# Main_Board_v1.net
KiCad netlist of a schematic drawn in EAGLE
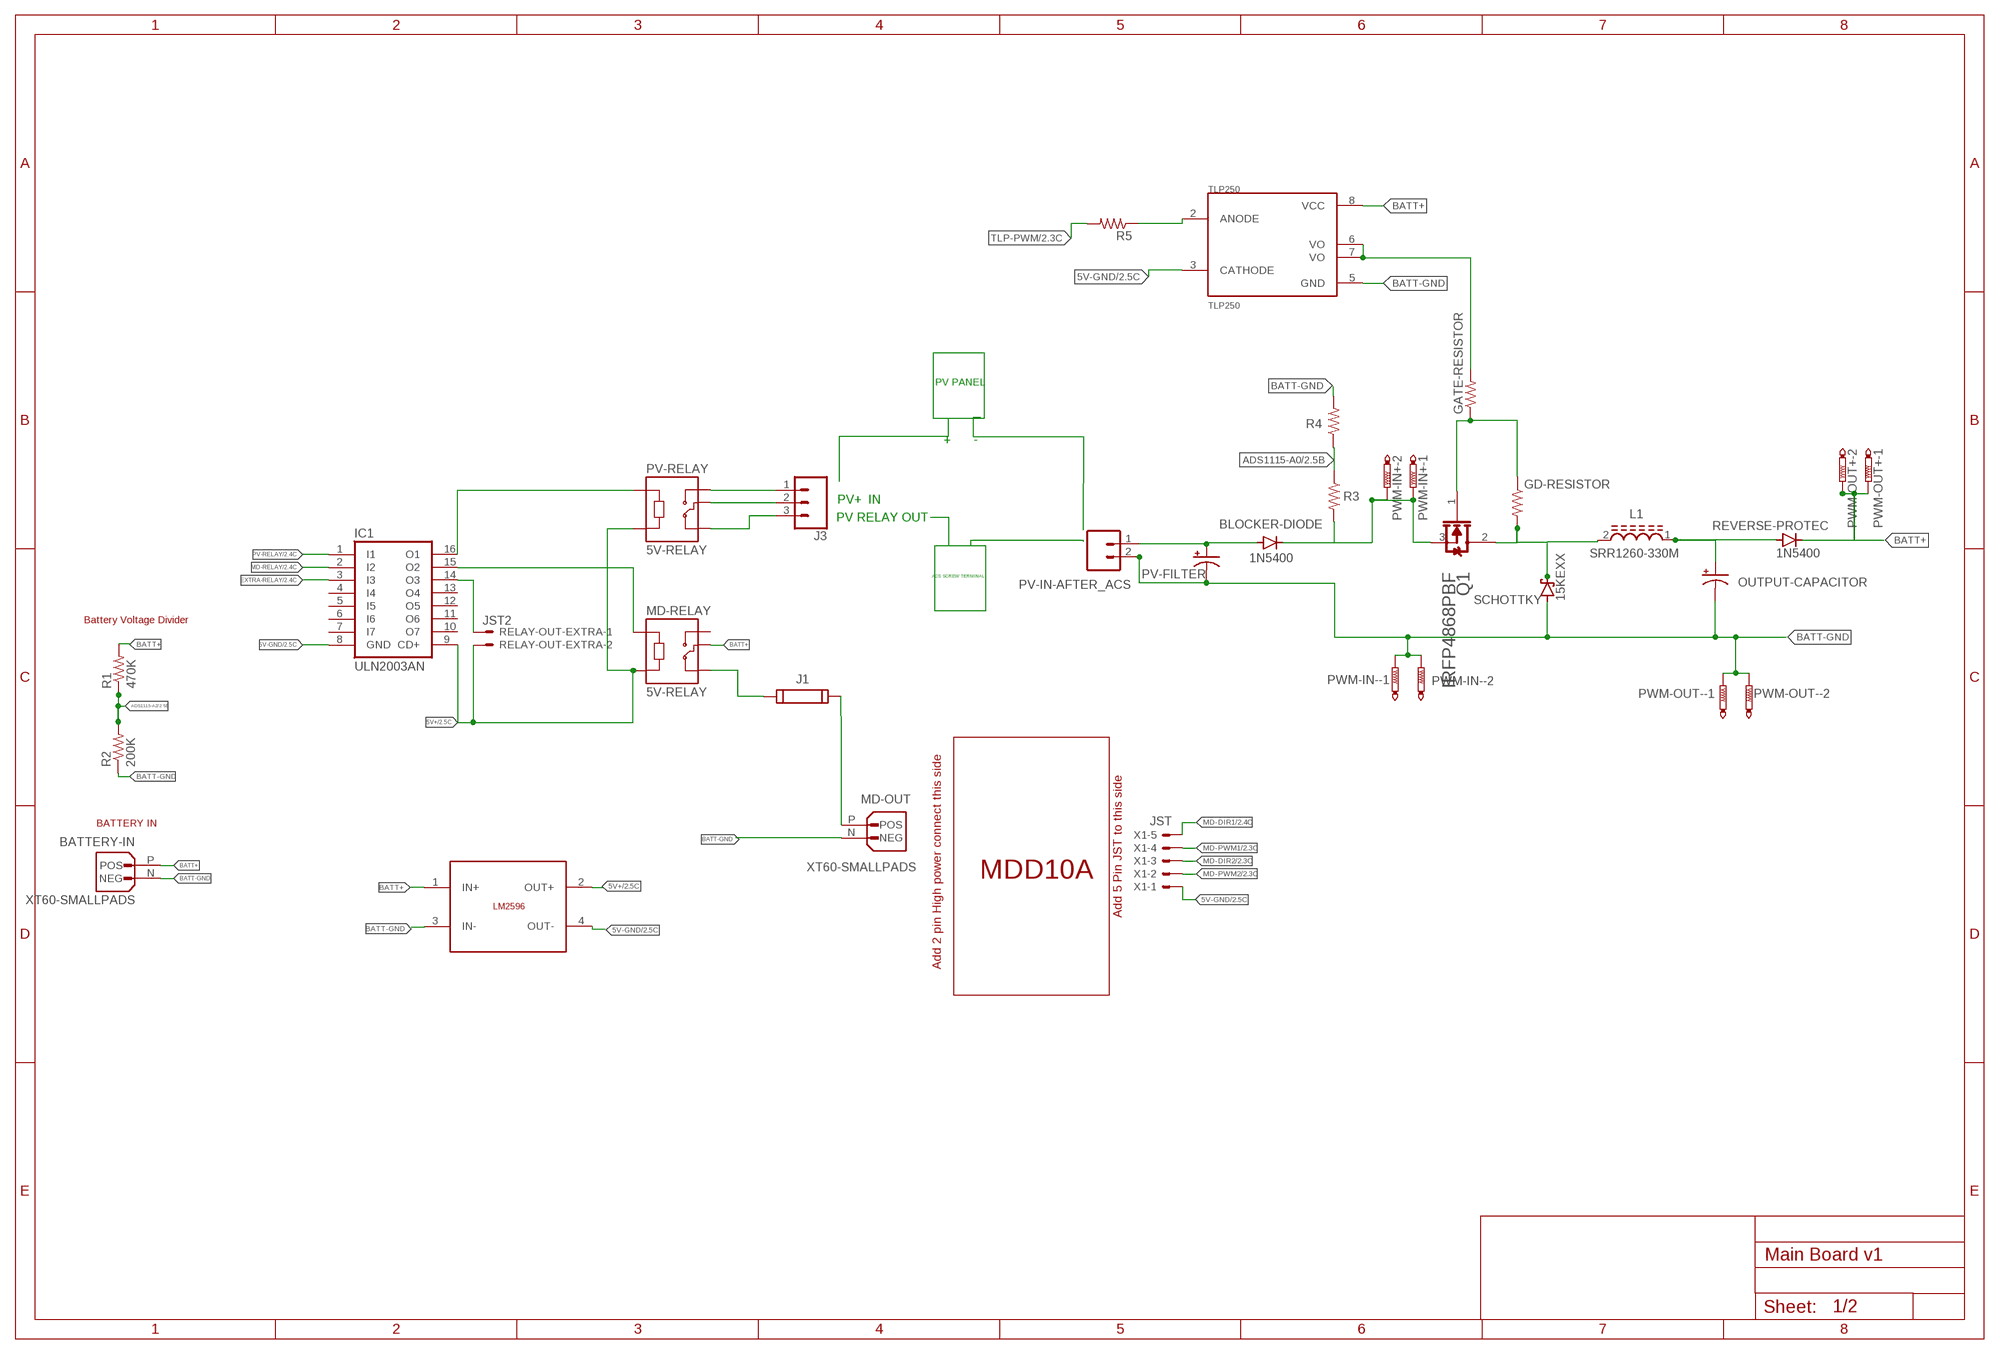
[diagram p0: schematic, sheet 1]
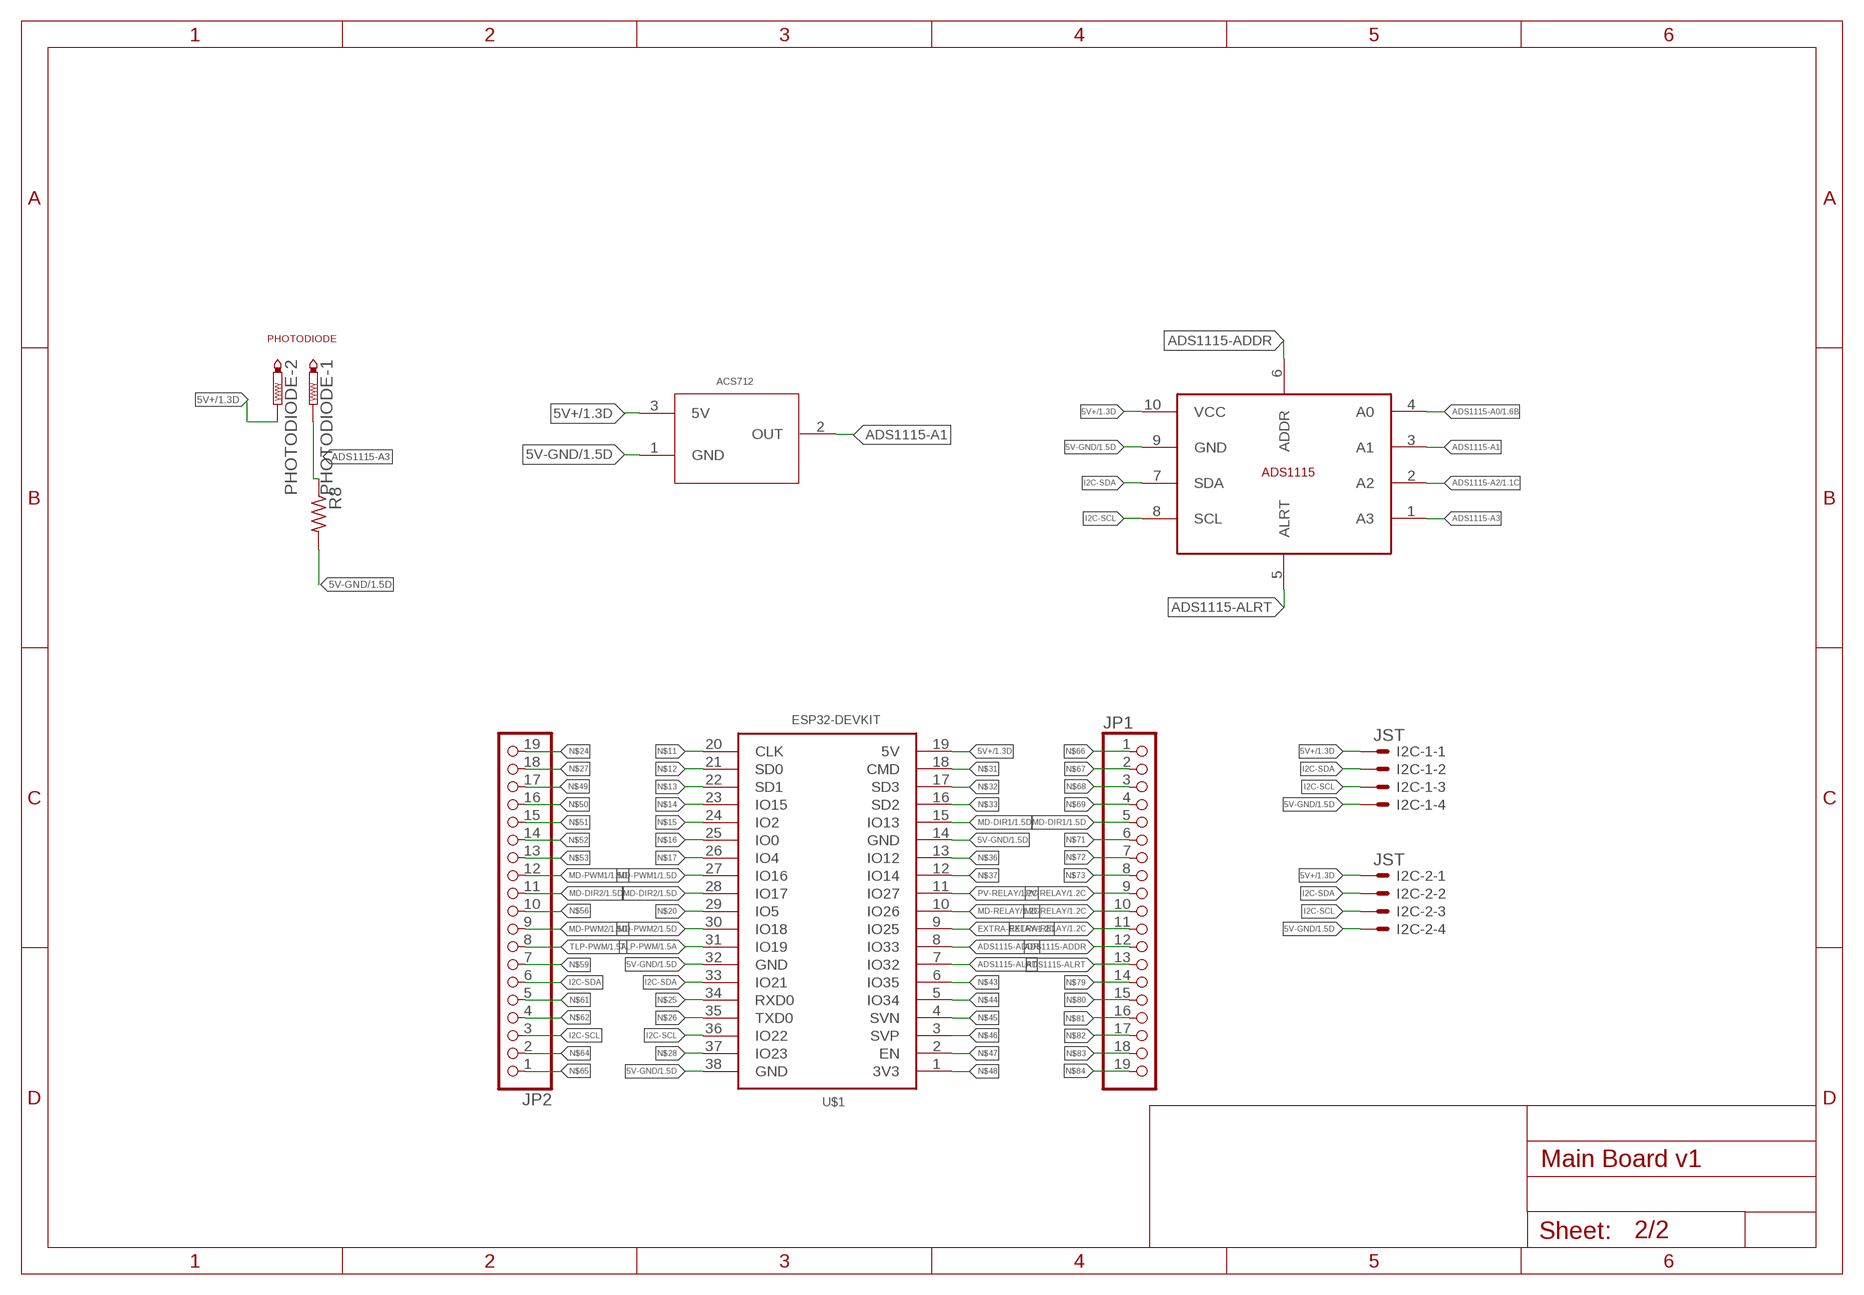
[diagram p1: schematic, sheet 2]

(export (version "E")
  (design (tool "Eeschema 10.0.6"))
  (components
    (comp (ref "I2C-1")
      (value "JST")
      (footprint "eagle-import:JST-XH-04-PACKAGE-LONG-PAD")
      (libsource (lib "eagle-import") (part "JST-XH-04-PIN-LONG-PAD"))
    )
    (comp (ref "I2C-2")
      (value "JST")
      (footprint "eagle-import:JST-XH-04-PACKAGE-LONG-PAD")
      (libsource (lib "eagle-import") (part "JST-XH-04-PIN-LONG-PAD"))
    )
    (comp (ref "JP1")
      (value "PINHD-1X19")
      (footprint "eagle-import:1X19")
      (libsource (lib "eagle-import") (part "PINHD-1X19"))
    )
    (comp (ref "JP2")
      (value "PINHD-1X19")
      (footprint "eagle-import:1X19")
      (libsource (lib "eagle-import") (part "PINHD-1X19"))
    )
    (comp (ref "PHOTODIODE")
      (value "PTR2")
      (footprint "eagle-import:P2-38-17")
      (libsource (lib "eagle-import") (part "PTR2"))
    )
    (comp (ref "R8")
      (value "R-US_0309/12")
      (footprint "eagle-import:0309_12")
      (libsource (lib "eagle-import") (part "R-US_0309/12"))
    )
    (comp (ref "U$1")
      (value "ESP32-DEVKIT")
      (footprint "eagle-import:ESP32-38PINS")
      (libsource (lib "eagle-import") (part "ESP32-DEVKIT"))
    )
    (comp (ref "U$3")
      (value "ACS712-MODULE")
      (footprint "eagle-import:ACS712-MODULE")
      (libsource (lib "eagle-import") (part "ACS712-MODULE"))
    )
    (comp (ref "U$4")
      (value "ADS1115-MODULE")
      (footprint "eagle-import:ADS1115-MODULE")
      (libsource (lib "eagle-import") (part "ADS1115-MODULE"))
    )
    (comp (ref "BATTERY-IN")
      (value "XT60-SMALLPADS")
      (footprint "eagle-import:XT-60-SMALLPADS")
      (libsource (lib "eagle-import") (part "XT60-SMALLPADS"))
    )
    (comp (ref "BLOCKER-DIODE")
      (value "1N5400")
      (footprint "eagle-import:DO201-15")
      (libsource (lib "eagle-import") (part "1N5400"))
    )
    (comp (ref "GATE-RESISTOR")
      (value "R-US_0309/12")
      (footprint "eagle-import:0309_12")
      (libsource (lib "eagle-import") (part "R-US_0309/12"))
    )
    (comp (ref "GD-RESISTOR")
      (value "R-US_0309/12")
      (footprint "eagle-import:0309_12")
      (libsource (lib "eagle-import") (part "R-US_0309/12"))
    )
    (comp (ref "IC1")
      (value "ULN2003AN")
      (footprint "eagle-import:DIL16")
      (fields (field (name "MF") "STMicroelectronics") (field (name "MP") "ULN2003A"))
      (libsource (lib "eagle-import") (part "ULN2003AN"))
    )
    (comp (ref "J1")
      (value "696101000002")
      (footprint "eagle-import:696101000002")
      (libsource (lib "eagle-import") (part "696101000002"))
    )
    (comp (ref "J3")
      (value "CONN_03SCREW_LOCK")
      (footprint "eagle-import:SCREWTERMINAL-3.5MM-3_LOCK.007S")
      (libsource (lib "eagle-import") (part "CONN_03SCREW_LOCK"))
    )
    (comp (ref "L1")
      (value "SRR1260-330M")
      (footprint "eagle-import:INDP125125X600N")
      (fields (field (name "MF") "Bourns"))
      (libsource (lib "eagle-import") (part "SRR1260-330M"))
    )
    (comp (ref "MD-OUT")
      (value "XT60-SMALLPADS")
      (footprint "eagle-import:XT-60-SMALLPADS")
      (libsource (lib "eagle-import") (part "XT60-SMALLPADS"))
    )
    (comp (ref "MD-RELAY")
      (value "5V-RELAY")
      (footprint "eagle-import:RELAY-SRD-05VDC-SL-C")
      (fields (field (name "MF") "Songle Relay") (field (name "MP") "SRD-05VDC-SL-C"))
      (libsource (lib "eagle-import") (part "5V-RELAY"))
    )
    (comp (ref "OUTPUT-CAPACITOR")
      (value "1000UF-RADIAL-5MM-25V-20%-NO-SILK")
      (footprint "eagle-import:CPOL-RADIAL-5MM-10MM-NS")
      (libsource (lib "eagle-import") (part "1000UF-RADIAL-5MM-25V-20%-NO-SILK"))
    )
    (comp (ref "PV-FILTER")
      (value "1000UF-RADIAL-5MM-25V-20%-NO-SILK")
      (footprint "eagle-import:CPOL-RADIAL-5MM-10MM-NS")
      (libsource (lib "eagle-import") (part "1000UF-RADIAL-5MM-25V-20%-NO-SILK"))
    )
    (comp (ref "PV-IN-AFTER_ACS")
      (value "CONN_023.5MM")
      (footprint "eagle-import:SCREWTERMINAL-3.5MM-2")
      (libsource (lib "eagle-import") (part "CONN_023.5MM"))
    )
    (comp (ref "PV-RELAY")
      (value "5V-RELAY")
      (footprint "eagle-import:RELAY-SRD-05VDC-SL-C")
      (fields (field (name "MF") "Songle Relay") (field (name "MP") "SRD-05VDC-SL-C"))
      (libsource (lib "eagle-import") (part "5V-RELAY"))
    )
    (comp (ref "PWM-IN+")
      (value "PTR2")
      (footprint "eagle-import:P2-38-17")
      (libsource (lib "eagle-import") (part "PTR2"))
    )
    (comp (ref "PWM-IN-")
      (value "PTR2")
      (footprint "eagle-import:P2-38-17")
      (libsource (lib "eagle-import") (part "PTR2"))
    )
    (comp (ref "PWM-OUT+")
      (value "PTR2")
      (footprint "eagle-import:P2-38-17")
      (libsource (lib "eagle-import") (part "PTR2"))
    )
    (comp (ref "PWM-OUT-")
      (value "PTR2")
      (footprint "eagle-import:P2-38-17")
      (libsource (lib "eagle-import") (part "PTR2"))
    )
    (comp (ref "Q1")
      (value "INFINEON_IRFP4868PBFINFINEON_IRFP4868PBF_0_0")
      (footprint "eagle-import:INFINEON_IRFP4868PBF_0")
      (fields
        (field (name "DIGIKEY_PART_NUMBER") "IRFP4868PBF-ND")
        (field (name "MF") "Infineon")
        (field (name "MOUSER_PART_NUMBER") "942-IRFP4868PBF")
      )
      (libsource (lib "eagle-import") (part "INFINEON_IRFP4868PBFINFINEON_IRFP4868PBF_0_0"))
    )
    (comp (ref "R1")
      (value "470K")
      (footprint "eagle-import:0309_12")
      (libsource (lib "eagle-import") (part "R-US_0309/12"))
    )
    (comp (ref "R2")
      (value "200K")
      (footprint "eagle-import:0309_12")
      (libsource (lib "eagle-import") (part "R-US_0309/12"))
    )
    (comp (ref "R3")
      (value "R-US_0309/12")
      (footprint "eagle-import:0309_12")
      (libsource (lib "eagle-import") (part "R-US_0309/12"))
    )
    (comp (ref "R4")
      (value "R-US_0309/12")
      (footprint "eagle-import:0309_12")
      (libsource (lib "eagle-import") (part "R-US_0309/12"))
    )
    (comp (ref "R5")
      (value "R-US_0309/12")
      (footprint "eagle-import:0309_12")
      (libsource (lib "eagle-import") (part "R-US_0309/12"))
    )
    (comp (ref "RELAY-OUT-EXTRA")
      (value "JST2")
      (footprint "eagle-import:JST-XH-02-PACKAGE-LONG-PAD")
      (libsource (lib "eagle-import") (part "JST-XH-02-PIN-LONG-PAD"))
    )
    (comp (ref "REVERSE-PROTEC")
      (value "1N5400")
      (footprint "eagle-import:DO201-15")
      (libsource (lib "eagle-import") (part "1N5400"))
    )
    (comp (ref "SCHOTTKY")
      (value "15KEXX")
      (footprint "eagle-import:CB429-17")
      (libsource (lib "eagle-import") (part "15KEXX"))
    )
    (comp (ref "TLP250")
      (value "TLP250")
      (footprint "eagle-import:DIP8")
      (fields (field (name "MF") "Toshiba") (field (name "MP") "TLP250(F)"))
      (libsource (lib "eagle-import") (part "TLP250"))
    )
    (comp (ref "U$2")
      (value "MDD10A-MODULE")
      (footprint "eagle-import:MDD10A")
      (libsource (lib "eagle-import") (part "MDD10A-MODULE"))
    )
    (comp (ref "U$5")
      (value "LM2596-MODULE")
      (footprint "eagle-import:LM2596-MODULE")
      (libsource (lib "eagle-import") (part "LM2596-MODULE"))
    )
    (comp (ref "X1")
      (value "JST")
      (footprint "eagle-import:JST-XH-05-PACKAGE-LONG-PAD")
      (libsource (lib "eagle-import") (part "JST-XH-05-PIN-LONG-PAD"))
    )
  )
  (nets
    (net (code "1") (name "5V+") (class "Default")
      (node (ref "I2C-1") (pin "1") (pinfunction "S_1") (pintype "passive"))
      (node (ref "I2C-2") (pin "1") (pinfunction "S_1") (pintype "passive"))
      (node (ref "IC1") (pin "9") (pinfunction "CD+_9") (pintype "passive"))
      (node (ref "MD-RELAY") (pin "A2") (pinfunction "A2_A2") (pintype "passive"))
      (node (ref "PHOTODIODE") (pin "TP-2") (pinfunction "TP_TP-2") (pintype "input"))
      (node (ref "PV-RELAY") (pin "A2") (pinfunction "A2_A2") (pintype "passive"))
      (node (ref "RELAY-OUT-EXTRA") (pin "2") (pinfunction "S_2") (pintype "passive"))
      (node (ref "U$1") (pin "19") (pinfunction "5V_19") (pintype "bidirectional"))
      (node (ref "U$3") (pin "3") (pinfunction "5V_3") (pintype "bidirectional"))
      (node (ref "U$4") (pin "10") (pinfunction "VCC_10") (pintype "bidirectional"))
      (node (ref "U$5") (pin "2") (pinfunction "OUT+_2") (pintype "bidirectional"))
    )
    (net (code "2") (name "5V-GND") (class "Default")
      (node (ref "I2C-1") (pin "4") (pinfunction "S_4") (pintype "passive"))
      (node (ref "I2C-2") (pin "4") (pinfunction "S_4") (pintype "passive"))
      (node (ref "IC1") (pin "8") (pinfunction "GND_8") (pintype "power_in"))
      (node (ref "R8") (pin "2") (pinfunction "2_2") (pintype "passive"))
      (node (ref "TLP250") (pin "3") (pinfunction "CATHODE_3") (pintype "passive"))
      (node (ref "U$1") (pin "14") (pinfunction "GND_14") (pintype "bidirectional"))
      (node (ref "U$1") (pin "32") (pinfunction "GND_32") (pintype "bidirectional"))
      (node (ref "U$1") (pin "38") (pinfunction "GND_38") (pintype "bidirectional"))
      (node (ref "U$3") (pin "1") (pinfunction "GND_1") (pintype "bidirectional"))
      (node (ref "U$4") (pin "9") (pinfunction "GND_9") (pintype "bidirectional"))
      (node (ref "U$5") (pin "4") (pinfunction "OUT-_4") (pintype "bidirectional"))
      (node (ref "X1") (pin "1") (pinfunction "S_1") (pintype "passive"))
    )
    (net (code "3") (name "ADS1115-A0") (class "Default")
      (node (ref "R3") (pin "1") (pinfunction "1_1") (pintype "passive"))
      (node (ref "R4") (pin "1") (pinfunction "1_1") (pintype "passive"))
      (node (ref "U$4") (pin "4") (pinfunction "A0_4") (pintype "bidirectional"))
    )
    (net (code "4") (name "ADS1115-A1") (class "Default")
      (node (ref "U$3") (pin "2") (pinfunction "OUT_2") (pintype "bidirectional"))
      (node (ref "U$4") (pin "3") (pinfunction "A1_3") (pintype "bidirectional"))
    )
    (net (code "5") (name "ADS1115-A2") (class "Default")
      (node (ref "R1") (pin "1") (pinfunction "1_1") (pintype "passive"))
      (node (ref "R2") (pin "2") (pinfunction "2_2") (pintype "passive"))
      (node (ref "U$4") (pin "2") (pinfunction "A2_2") (pintype "bidirectional"))
    )
    (net (code "6") (name "ADS1115-A3") (class "Default")
      (node (ref "PHOTODIODE") (pin "TP-1") (pinfunction "TP_TP-1") (pintype "input"))
      (node (ref "R8") (pin "1") (pinfunction "1_1") (pintype "passive"))
      (node (ref "U$4") (pin "1") (pinfunction "A3_1") (pintype "bidirectional"))
    )
    (net (code "7") (name "ADS1115-ADDR") (class "Default")
      (node (ref "JP1") (pin "12") (pinfunction "12_12") (pintype "passive"))
      (node (ref "U$1") (pin "8") (pinfunction "IO33_8") (pintype "bidirectional"))
      (node (ref "U$4") (pin "6") (pinfunction "ADDR_6") (pintype "bidirectional"))
    )
    (net (code "8") (name "ADS1115-ALRT") (class "Default")
      (node (ref "JP1") (pin "13") (pinfunction "13_13") (pintype "passive"))
      (node (ref "U$1") (pin "7") (pinfunction "IO32_7") (pintype "bidirectional"))
      (node (ref "U$4") (pin "5") (pinfunction "ALRT_5") (pintype "bidirectional"))
    )
    (net (code "9") (name "BATT+") (class "Default")
      (node (ref "BATTERY-IN") (pin "P") (pinfunction "POS_P") (pintype "passive"))
      (node (ref "MD-RELAY") (pin "COM") (pinfunction "COM_COM") (pintype "passive"))
      (node (ref "PWM-OUT+") (pin "TP-1") (pinfunction "TP_TP-1") (pintype "input"))
      (node (ref "PWM-OUT+") (pin "TP-2") (pinfunction "TP_TP-2") (pintype "input"))
      (node (ref "R1") (pin "2") (pinfunction "2_2") (pintype "passive"))
      (node (ref "REVERSE-PROTEC") (pin "C") (pinfunction "C_C") (pintype "passive"))
      (node (ref "TLP250") (pin "8") (pinfunction "VCC_8") (pintype "power_in"))
      (node (ref "U$5") (pin "1") (pinfunction "IN+_1") (pintype "bidirectional"))
    )
    (net (code "10") (name "BATT-GND") (class "Default")
      (node (ref "BATTERY-IN") (pin "N") (pinfunction "NEG_N") (pintype "passive"))
      (node (ref "MD-OUT") (pin "N") (pinfunction "NEG_N") (pintype "passive"))
      (node (ref "OUTPUT-CAPACITOR") (pin "-") (pinfunction "-_-") (pintype "passive"))
      (node (ref "PV-FILTER") (pin "-") (pinfunction "-_-") (pintype "passive"))
      (node (ref "PV-IN-AFTER_ACS") (pin "2") (pinfunction "2_2") (pintype "passive"))
      (node (ref "PWM-IN-") (pin "TP-1") (pinfunction "TP_TP-1") (pintype "input"))
      (node (ref "PWM-IN-") (pin "TP-2") (pinfunction "TP_TP-2") (pintype "input"))
      (node (ref "PWM-OUT-") (pin "TP-1") (pinfunction "TP_TP-1") (pintype "input"))
      (node (ref "PWM-OUT-") (pin "TP-2") (pinfunction "TP_TP-2") (pintype "input"))
      (node (ref "R2") (pin "1") (pinfunction "1_1") (pintype "passive"))
      (node (ref "R4") (pin "2") (pinfunction "2_2") (pintype "passive"))
      (node (ref "SCHOTTKY") (pin "A") (pinfunction "A_A") (pintype "passive"))
      (node (ref "TLP250") (pin "5") (pinfunction "GND_5") (pintype "power_in"))
      (node (ref "U$5") (pin "3") (pinfunction "IN-_3") (pintype "bidirectional"))
    )
    (net (code "11") (name "EXTRA-RELAY") (class "Default")
      (node (ref "IC1") (pin "3") (pinfunction "I3_3") (pintype "input"))
      (node (ref "JP1") (pin "11") (pinfunction "11_11") (pintype "passive"))
      (node (ref "U$1") (pin "9") (pinfunction "IO25_9") (pintype "bidirectional"))
    )
    (net (code "12") (name "I2C-SCL") (class "Default")
      (node (ref "I2C-1") (pin "3") (pinfunction "S_3") (pintype "passive"))
      (node (ref "I2C-2") (pin "3") (pinfunction "S_3") (pintype "passive"))
      (node (ref "JP2") (pin "3") (pinfunction "3_3") (pintype "passive"))
      (node (ref "U$1") (pin "36") (pinfunction "IO22_36") (pintype "bidirectional"))
      (node (ref "U$4") (pin "8") (pinfunction "SCL_8") (pintype "bidirectional"))
    )
    (net (code "13") (name "I2C-SDA") (class "Default")
      (node (ref "I2C-1") (pin "2") (pinfunction "S_2") (pintype "passive"))
      (node (ref "I2C-2") (pin "2") (pinfunction "S_2") (pintype "passive"))
      (node (ref "JP2") (pin "6") (pinfunction "6_6") (pintype "passive"))
      (node (ref "U$1") (pin "33") (pinfunction "IO21_33") (pintype "bidirectional"))
      (node (ref "U$4") (pin "7") (pinfunction "SDA_7") (pintype "bidirectional"))
    )
    (net (code "14") (name "MD-DIR1") (class "Default")
      (node (ref "JP1") (pin "5") (pinfunction "5_5") (pintype "passive"))
      (node (ref "U$1") (pin "15") (pinfunction "IO13_15") (pintype "bidirectional"))
      (node (ref "X1") (pin "5") (pinfunction "S_5") (pintype "passive"))
    )
    (net (code "15") (name "MD-DIR2") (class "Default")
      (node (ref "JP2") (pin "11") (pinfunction "11_11") (pintype "passive"))
      (node (ref "U$1") (pin "28") (pinfunction "IO17_28") (pintype "bidirectional"))
      (node (ref "X1") (pin "3") (pinfunction "S_3") (pintype "passive"))
    )
    (net (code "16") (name "MD-PWM1") (class "Default")
      (node (ref "JP2") (pin "12") (pinfunction "12_12") (pintype "passive"))
      (node (ref "U$1") (pin "27") (pinfunction "IO16_27") (pintype "bidirectional"))
      (node (ref "X1") (pin "4") (pinfunction "S_4") (pintype "passive"))
    )
    (net (code "17") (name "MD-PWM2") (class "Default")
      (node (ref "JP2") (pin "9") (pinfunction "9_9") (pintype "passive"))
      (node (ref "U$1") (pin "30") (pinfunction "IO18_30") (pintype "bidirectional"))
      (node (ref "X1") (pin "2") (pinfunction "S_2") (pintype "passive"))
    )
    (net (code "18") (name "MD-RELAY") (class "Default")
      (node (ref "IC1") (pin "2") (pinfunction "I2_2") (pintype "input"))
      (node (ref "JP1") (pin "10") (pinfunction "10_10") (pintype "passive"))
      (node (ref "U$1") (pin "10") (pinfunction "IO26_10") (pintype "bidirectional"))
    )
    (net (code "19") (name "N$11") (class "Default")
      (node (ref "U$1") (pin "20") (pinfunction "CLK_20") (pintype "bidirectional"))
    )
    (net (code "20") (name "N$12") (class "Default")
      (node (ref "U$1") (pin "21") (pinfunction "SD0_21") (pintype "bidirectional"))
    )
    (net (code "21") (name "N$13") (class "Default")
      (node (ref "U$1") (pin "22") (pinfunction "SD1_22") (pintype "bidirectional"))
    )
    (net (code "22") (name "N$14") (class "Default")
      (node (ref "U$1") (pin "23") (pinfunction "IO15_23") (pintype "bidirectional"))
    )
    (net (code "23") (name "N$15") (class "Default")
      (node (ref "U$1") (pin "24") (pinfunction "IO2_24") (pintype "bidirectional"))
    )
    (net (code "24") (name "N$16") (class "Default")
      (node (ref "U$1") (pin "25") (pinfunction "IO0_25") (pintype "bidirectional"))
    )
    (net (code "25") (name "N$17") (class "Default")
      (node (ref "U$1") (pin "26") (pinfunction "IO4_26") (pintype "bidirectional"))
    )
    (net (code "26") (name "N$20") (class "Default")
      (node (ref "U$1") (pin "29") (pinfunction "IO5_29") (pintype "bidirectional"))
    )
    (net (code "27") (name "N$24") (class "Default")
      (node (ref "JP2") (pin "19") (pinfunction "19_19") (pintype "passive"))
    )
    (net (code "28") (name "N$25") (class "Default")
      (node (ref "U$1") (pin "34") (pinfunction "RXD0_34") (pintype "bidirectional"))
    )
    (net (code "29") (name "N$26") (class "Default")
      (node (ref "U$1") (pin "35") (pinfunction "TXD0_35") (pintype "bidirectional"))
    )
    (net (code "30") (name "N$27") (class "Default")
      (node (ref "JP2") (pin "18") (pinfunction "18_18") (pintype "passive"))
    )
    (net (code "31") (name "N$28") (class "Default")
      (node (ref "U$1") (pin "37") (pinfunction "IO23_37") (pintype "bidirectional"))
    )
    (net (code "32") (name "N$31") (class "Default")
      (node (ref "U$1") (pin "18") (pinfunction "CMD_18") (pintype "bidirectional"))
    )
    (net (code "33") (name "N$32") (class "Default")
      (node (ref "U$1") (pin "17") (pinfunction "SD3_17") (pintype "bidirectional"))
    )
    (net (code "34") (name "N$33") (class "Default")
      (node (ref "U$1") (pin "16") (pinfunction "SD2_16") (pintype "bidirectional"))
    )
    (net (code "35") (name "N$36") (class "Default")
      (node (ref "U$1") (pin "13") (pinfunction "IO12_13") (pintype "bidirectional"))
    )
    (net (code "36") (name "N$37") (class "Default")
      (node (ref "U$1") (pin "12") (pinfunction "IO14_12") (pintype "bidirectional"))
    )
    (net (code "37") (name "N$43") (class "Default")
      (node (ref "U$1") (pin "6") (pinfunction "IO35_6") (pintype "bidirectional"))
    )
    (net (code "38") (name "N$44") (class "Default")
      (node (ref "U$1") (pin "5") (pinfunction "IO34_5") (pintype "bidirectional"))
    )
    (net (code "39") (name "N$45") (class "Default")
      (node (ref "U$1") (pin "4") (pinfunction "SVN_4") (pintype "bidirectional"))
    )
    (net (code "40") (name "N$46") (class "Default")
      (node (ref "U$1") (pin "3") (pinfunction "SVP_3") (pintype "bidirectional"))
    )
    (net (code "41") (name "N$47") (class "Default")
      (node (ref "U$1") (pin "2") (pinfunction "EN_2") (pintype "bidirectional"))
    )
    (net (code "42") (name "N$48") (class "Default")
      (node (ref "U$1") (pin "1") (pinfunction "3V3_1") (pintype "bidirectional"))
    )
    (net (code "43") (name "N$49") (class "Default")
      (node (ref "JP2") (pin "17") (pinfunction "17_17") (pintype "passive"))
    )
    (net (code "44") (name "N$50") (class "Default")
      (node (ref "JP2") (pin "16") (pinfunction "16_16") (pintype "passive"))
    )
    (net (code "45") (name "N$51") (class "Default")
      (node (ref "JP2") (pin "15") (pinfunction "15_15") (pintype "passive"))
    )
    (net (code "46") (name "N$52") (class "Default")
      (node (ref "JP2") (pin "14") (pinfunction "14_14") (pintype "passive"))
    )
    (net (code "47") (name "N$53") (class "Default")
      (node (ref "JP2") (pin "13") (pinfunction "13_13") (pintype "passive"))
    )
    (net (code "48") (name "N$56") (class "Default")
      (node (ref "JP2") (pin "10") (pinfunction "10_10") (pintype "passive"))
    )
    (net (code "49") (name "N$59") (class "Default")
      (node (ref "JP2") (pin "7") (pinfunction "7_7") (pintype "passive"))
    )
    (net (code "50") (name "N$61") (class "Default")
      (node (ref "JP2") (pin "5") (pinfunction "5_5") (pintype "passive"))
    )
    (net (code "51") (name "N$62") (class "Default")
      (node (ref "JP2") (pin "4") (pinfunction "4_4") (pintype "passive"))
    )
    (net (code "52") (name "N$64") (class "Default")
      (node (ref "JP2") (pin "2") (pinfunction "2_2") (pintype "passive"))
    )
    (net (code "53") (name "N$65") (class "Default")
      (node (ref "JP2") (pin "1") (pinfunction "1_1") (pintype "passive"))
    )
    (net (code "54") (name "N$66") (class "Default")
      (node (ref "JP1") (pin "1") (pinfunction "1_1") (pintype "passive"))
    )
    (net (code "55") (name "N$67") (class "Default")
      (node (ref "JP1") (pin "2") (pinfunction "2_2") (pintype "passive"))
    )
    (net (code "56") (name "N$68") (class "Default")
      (node (ref "JP1") (pin "3") (pinfunction "3_3") (pintype "passive"))
    )
    (net (code "57") (name "N$69") (class "Default")
      (node (ref "JP1") (pin "4") (pinfunction "4_4") (pintype "passive"))
    )
    (net (code "58") (name "N$71") (class "Default")
      (node (ref "JP1") (pin "6") (pinfunction "6_6") (pintype "passive"))
    )
    (net (code "59") (name "N$72") (class "Default")
      (node (ref "JP1") (pin "7") (pinfunction "7_7") (pintype "passive"))
    )
    (net (code "60") (name "N$73") (class "Default")
      (node (ref "JP1") (pin "8") (pinfunction "8_8") (pintype "passive"))
    )
    (net (code "61") (name "N$79") (class "Default")
      (node (ref "JP1") (pin "14") (pinfunction "14_14") (pintype "passive"))
    )
    (net (code "62") (name "N$80") (class "Default")
      (node (ref "JP1") (pin "15") (pinfunction "15_15") (pintype "passive"))
    )
    (net (code "63") (name "N$81") (class "Default")
      (node (ref "JP1") (pin "16") (pinfunction "16_16") (pintype "passive"))
    )
    (net (code "64") (name "N$82") (class "Default")
      (node (ref "JP1") (pin "17") (pinfunction "17_17") (pintype "passive"))
    )
    (net (code "65") (name "N$83") (class "Default")
      (node (ref "JP1") (pin "18") (pinfunction "18_18") (pintype "passive"))
    )
    (net (code "66") (name "N$84") (class "Default")
      (node (ref "JP1") (pin "19") (pinfunction "19_19") (pintype "passive"))
    )
    (net (code "67") (name "Net-(BLOCKER-DIODE-PadA)") (class "Default")
      (node (ref "BLOCKER-DIODE") (pin "A") (pinfunction "A_A") (pintype "passive"))
      (node (ref "PV-FILTER") (pin "+") (pinfunction "+_+") (pintype "passive"))
      (node (ref "PV-IN-AFTER_ACS") (pin "1") (pinfunction "1_1") (pintype "passive"))
    )
    (net (code "68") (name "Net-(GATE-RESISTOR-Pad2)") (class "Default")
      (node (ref "GATE-RESISTOR") (pin "2") (pinfunction "2_2") (pintype "passive"))
      (node (ref "TLP250") (pin "6") (pinfunction "VO_6") (pintype "output"))
      (node (ref "TLP250") (pin "7") (pinfunction "VO_7") (pintype "output"))
    )
    (net (code "69") (name "Net-(IC1-O1)") (class "Default")
      (node (ref "IC1") (pin "16") (pinfunction "O1_16") (pintype "open_collector"))
      (node (ref "PV-RELAY") (pin "A1") (pinfunction "A1_A1") (pintype "passive"))
    )
    (net (code "70") (name "Net-(IC1-O2)") (class "Default")
      (node (ref "IC1") (pin "15") (pinfunction "O2_15") (pintype "open_collector"))
      (node (ref "MD-RELAY") (pin "A1") (pinfunction "A1_A1") (pintype "passive"))
    )
    (net (code "71") (name "Net-(IC1-O3)") (class "Default")
      (node (ref "IC1") (pin "14") (pinfunction "O3_14") (pintype "open_collector"))
      (node (ref "RELAY-OUT-EXTRA") (pin "1") (pinfunction "S_1") (pintype "passive"))
    )
    (net (code "72") (name "Net-(J1-Pad1)") (class "Default")
      (node (ref "J1") (pin "1") (pinfunction "1_1") (pintype "passive"))
      (node (ref "MD-RELAY") (pin "NC") (pinfunction "NC_NC") (pintype "passive"))
    )
    (net (code "73") (name "Net-(J3-Pad1)") (class "Default")
      (node (ref "J3") (pin "1") (pinfunction "1_1") (pintype "passive"))
      (node (ref "PV-RELAY") (pin "NO") (pinfunction "NO_NO") (pintype "passive"))
    )
    (net (code "74") (name "Net-(J3-Pad2)") (class "Default")
      (node (ref "J3") (pin "2") (pinfunction "2_2") (pintype "passive"))
      (node (ref "PV-RELAY") (pin "COM") (pinfunction "COM_COM") (pintype "passive"))
    )
    (net (code "75") (name "Net-(J3-Pad3)") (class "Default")
      (node (ref "J3") (pin "3") (pinfunction "3_3") (pintype "passive"))
      (node (ref "PV-RELAY") (pin "NC") (pinfunction "NC_NC") (pintype "passive"))
    )
    (net (code "76") (name "Net-(L1-Pad1)") (class "Default")
      (node (ref "L1") (pin "1") (pinfunction "1_1") (pintype "passive"))
      (node (ref "OUTPUT-CAPACITOR") (pin "+") (pinfunction "+_+") (pintype "passive"))
      (node (ref "REVERSE-PROTEC") (pin "A") (pinfunction "A_A") (pintype "passive"))
    )
    (net (code "77") (name "Net-(MD-OUT-POS)") (class "Default")
      (node (ref "J1") (pin "2") (pinfunction "2_2") (pintype "passive"))
      (node (ref "MD-OUT") (pin "P") (pinfunction "POS_P") (pintype "passive"))
    )
    (net (code "78") (name "Net-(PWM-IN+A-TP)") (class "Default")
      (node (ref "BLOCKER-DIODE") (pin "C") (pinfunction "C_C") (pintype "passive"))
      (node (ref "PWM-IN+") (pin "TP-1") (pinfunction "TP_TP-1") (pintype "input"))
      (node (ref "PWM-IN+") (pin "TP-2") (pinfunction "TP_TP-2") (pintype "input"))
      (node (ref "Q1") (pin "3") (pinfunction "S_3") (pintype "passive"))
      (node (ref "R3") (pin "2") (pinfunction "2_2") (pintype "passive"))
    )
    (net (code "79") (name "Net-(Q1-D)") (class "Default")
      (node (ref "GD-RESISTOR") (pin "2") (pinfunction "2_2") (pintype "passive"))
      (node (ref "L1") (pin "2") (pinfunction "2_2") (pintype "passive"))
      (node (ref "Q1") (pin "2") (pinfunction "D_2") (pintype "passive"))
      (node (ref "SCHOTTKY") (pin "C") (pinfunction "C_C") (pintype "passive"))
    )
    (net (code "80") (name "Net-(Q1-G)") (class "Default")
      (node (ref "GATE-RESISTOR") (pin "1") (pinfunction "1_1") (pintype "passive"))
      (node (ref "GD-RESISTOR") (pin "1") (pinfunction "1_1") (pintype "passive"))
      (node (ref "Q1") (pin "1") (pinfunction "G_1") (pintype "passive"))
    )
    (net (code "81") (name "Net-(TLP250-ANODE)") (class "Default")
      (node (ref "R5") (pin "1") (pinfunction "1_1") (pintype "passive"))
      (node (ref "TLP250") (pin "2") (pinfunction "ANODE_2") (pintype "passive"))
    )
    (net (code "82") (name "PV-RELAY") (class "Default")
      (node (ref "IC1") (pin "1") (pinfunction "I1_1") (pintype "input"))
      (node (ref "JP1") (pin "9") (pinfunction "9_9") (pintype "passive"))
      (node (ref "U$1") (pin "11") (pinfunction "IO27_11") (pintype "bidirectional"))
    )
    (net (code "83") (name "TLP-PWM") (class "Default")
      (node (ref "JP2") (pin "8") (pinfunction "8_8") (pintype "passive"))
      (node (ref "R5") (pin "2") (pinfunction "2_2") (pintype "passive"))
      (node (ref "U$1") (pin "31") (pinfunction "IO19_31") (pintype "bidirectional"))
    )
    (net (code "84") (name "unconnected-(IC1-I4-Pad4)") (class "Default")
      (node (ref "IC1") (pin "4") (pinfunction "I4_4") (pintype "input"))
    )
    (net (code "85") (name "unconnected-(IC1-I5-Pad5)") (class "Default")
      (node (ref "IC1") (pin "5") (pinfunction "I5_5") (pintype "input"))
    )
    (net (code "86") (name "unconnected-(IC1-I6-Pad6)") (class "Default")
      (node (ref "IC1") (pin "6") (pinfunction "I6_6") (pintype "input"))
    )
    (net (code "87") (name "unconnected-(IC1-I7-Pad7)") (class "Default")
      (node (ref "IC1") (pin "7") (pinfunction "I7_7") (pintype "input"))
    )
    (net (code "88") (name "unconnected-(IC1-O4-Pad13)") (class "Default")
      (node (ref "IC1") (pin "13") (pinfunction "O4_13") (pintype "open_collector"))
    )
    (net (code "89") (name "unconnected-(IC1-O5-Pad12)") (class "Default")
      (node (ref "IC1") (pin "12") (pinfunction "O5_12") (pintype "open_collector"))
    )
    (net (code "90") (name "unconnected-(IC1-O6-Pad11)") (class "Default")
      (node (ref "IC1") (pin "11") (pinfunction "O6_11") (pintype "open_collector"))
    )
    (net (code "91") (name "unconnected-(IC1-O7-Pad10)") (class "Default")
      (node (ref "IC1") (pin "10") (pinfunction "O7_10") (pintype "open_collector"))
    )
    (net (code "92") (name "unconnected-(MD-RELAY-PadNO)") (class "Default")
      (node (ref "MD-RELAY") (pin "NO") (pinfunction "NO_NO") (pintype "passive"))
    )
  )
)
